# Motherboard.net
KiCad netlist of a schematic drawn in EAGLE
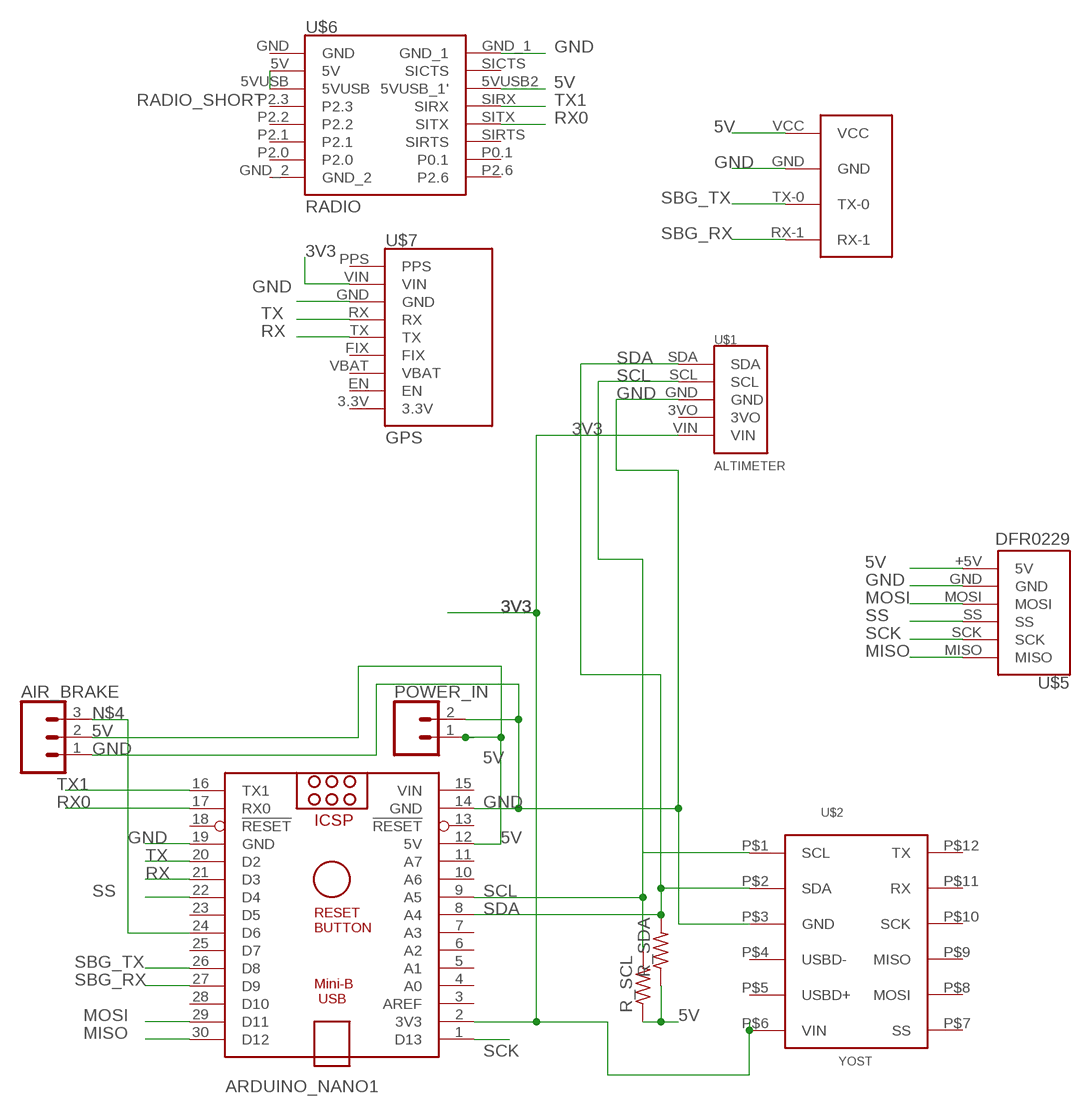
[diagram p0: schematic, sheet 1]

(export (version "E")
  (design (tool "Eeschema 10.0.6"))
  (components
    (comp (ref "AIR_BRAKE")
      (value "CONN_03")
      (footprint "eagle-import:1X03")
      (libsource (lib "eagle-import") (part "CONN_03"))
    )
    (comp (ref "ARDUINO_NANO1")
      (value "ARDUINO_NANO")
      (footprint "eagle-import:ARDUINO_NANO")
      (libsource (lib "eagle-import") (part "ARDUINO_NANO"))
    )
    (comp (ref "POWER_IN")
      (value "CONN_023.5MM")
      (footprint "eagle-import:SCREWTERMINAL-3.5MM-2")
      (libsource (lib "eagle-import") (part "CONN_023.5MM"))
    )
    (comp (ref "R_SCL")
      (value "R-US_R0603")
      (footprint "eagle-import:R0603")
      (libsource (lib "eagle-import") (part "R-US_R0603"))
    )
    (comp (ref "R_SDA")
      (value "R-US_R0603")
      (footprint "eagle-import:R0603")
      (libsource (lib "eagle-import") (part "R-US_R0603"))
    )
    (comp (ref "U$1")
      (value "ALTIMETER")
      (footprint "eagle-import:ALTIMETER")
      (libsource (lib "eagle-import") (part "ALTIMETER"))
    )
    (comp (ref "U$2")
      (value "YOST")
      (footprint "eagle-import:YOST")
      (libsource (lib "eagle-import") (part "YOST"))
    )
    (comp (ref "U$3")
      (value "RS232")
      (footprint "eagle-import:RS232")
      (libsource (lib "eagle-import") (part "RS232"))
    )
    (comp (ref "U$5")
      (value "DFR0229")
      (footprint "eagle-import:DFR0229")
      (libsource (lib "eagle-import") (part "DFR0229"))
    )
    (comp (ref "U$6")
      (value "RADIO")
      (footprint "eagle-import:RADIO")
      (libsource (lib "eagle-import") (part "RADIO"))
    )
    (comp (ref "U$7")
      (value "GPS")
      (footprint "eagle-import:GPS")
      (libsource (lib "eagle-import") (part "GPS"))
    )
  )
  (nets
    (net (code "1") (name "/3V3") (class "Default")
      (node (ref "ARDUINO_NANO1") (pin "2") (pinfunction "3V3_2") (pintype "output"))
      (node (ref "U$1") (pin "VIN") (pinfunction "VIN_VIN") (pintype "bidirectional"))
      (node (ref "U$2") (pin "P$6") (pinfunction "VIN_P$6") (pintype "bidirectional"))
      (node (ref "U$7") (pin "VIN") (pinfunction "VIN_VIN") (pintype "bidirectional"))
    )
    (net (code "2") (name "/5V") (class "Default")
      (node (ref "AIR_BRAKE") (pin "2") (pinfunction "2_2") (pintype "passive"))
      (node (ref "ARDUINO_NANO1") (pin "12") (pinfunction "5V_12") (pintype "power_in"))
      (node (ref "POWER_IN") (pin "1") (pinfunction "1_1") (pintype "passive"))
      (node (ref "R_SCL") (pin "1") (pinfunction "1_1") (pintype "passive"))
      (node (ref "R_SDA") (pin "1") (pinfunction "1_1") (pintype "passive"))
      (node (ref "U$3") (pin "VCC") (pinfunction "VCC_VCC") (pintype "bidirectional"))
      (node (ref "U$5") (pin "+5V") (pinfunction "5V_+5V") (pintype "bidirectional"))
      (node (ref "U$6") (pin "5VUSB2") (pinfunction "5VUSB_1'_5VUSB2") (pintype "bidirectional"))
    )
    (net (code "3") (name "/GND") (class "Default")
      (node (ref "AIR_BRAKE") (pin "1") (pinfunction "1_1") (pintype "passive"))
      (node (ref "ARDUINO_NANO1") (pin "14") (pinfunction "GND_14") (pintype "power_in"))
      (node (ref "ARDUINO_NANO1") (pin "19") (pinfunction "GND_19") (pintype "power_in"))
      (node (ref "POWER_IN") (pin "2") (pinfunction "2_2") (pintype "passive"))
      (node (ref "U$1") (pin "GND") (pinfunction "GND_GND") (pintype "bidirectional"))
      (node (ref "U$2") (pin "P$3") (pinfunction "GND_P$3") (pintype "bidirectional"))
      (node (ref "U$3") (pin "GND") (pinfunction "GND_GND") (pintype "bidirectional"))
      (node (ref "U$5") (pin "GND") (pinfunction "GND_GND") (pintype "bidirectional"))
      (node (ref "U$6") (pin "GND_1") (pinfunction "GND_1_GND_1") (pintype "bidirectional"))
      (node (ref "U$7") (pin "GND") (pinfunction "GND_GND") (pintype "bidirectional"))
    )
    (net (code "4") (name "/MISO") (class "Default")
      (node (ref "ARDUINO_NANO1") (pin "30") (pinfunction "D12_30") (pintype "bidirectional"))
      (node (ref "U$5") (pin "MISO") (pinfunction "MISO_MISO") (pintype "bidirectional"))
    )
    (net (code "5") (name "/MOSI") (class "Default")
      (node (ref "ARDUINO_NANO1") (pin "29") (pinfunction "D11_29") (pintype "bidirectional"))
      (node (ref "U$5") (pin "MOSI") (pinfunction "MOSI_MOSI") (pintype "bidirectional"))
    )
    (net (code "6") (name "/N$4") (class "Default")
      (node (ref "AIR_BRAKE") (pin "3") (pinfunction "3_3") (pintype "passive"))
      (node (ref "ARDUINO_NANO1") (pin "24") (pinfunction "D6_24") (pintype "bidirectional"))
    )
    (net (code "7") (name "/RADIO_SHORT") (class "Default")
      (node (ref "U$6") (pin "5V") (pinfunction "5V_5V") (pintype "bidirectional"))
      (node (ref "U$6") (pin "5VUSB") (pinfunction "5VUSB_5VUSB") (pintype "bidirectional"))
    )
    (net (code "8") (name "/RX") (class "Default")
      (node (ref "ARDUINO_NANO1") (pin "21") (pinfunction "D3_21") (pintype "bidirectional"))
      (node (ref "U$7") (pin "TX") (pinfunction "TX_TX") (pintype "bidirectional"))
    )
    (net (code "9") (name "/RX0") (class "Default")
      (node (ref "ARDUINO_NANO1") (pin "17") (pinfunction "RX0_17") (pintype "bidirectional"))
      (node (ref "U$6") (pin "SITX") (pinfunction "SITX_SITX") (pintype "bidirectional"))
    )
    (net (code "10") (name "/SBG_RX") (class "Default")
      (node (ref "ARDUINO_NANO1") (pin "27") (pinfunction "D9_27") (pintype "bidirectional"))
      (node (ref "U$3") (pin "RX-1") (pinfunction "RX-1_RX-1") (pintype "bidirectional"))
    )
    (net (code "11") (name "/SBG_TX") (class "Default")
      (node (ref "ARDUINO_NANO1") (pin "26") (pinfunction "D8_26") (pintype "bidirectional"))
      (node (ref "U$3") (pin "TX-0") (pinfunction "TX-0_TX-0") (pintype "bidirectional"))
    )
    (net (code "12") (name "/SCK") (class "Default")
      (node (ref "ARDUINO_NANO1") (pin "1") (pinfunction "D13_1") (pintype "bidirectional"))
      (node (ref "U$5") (pin "SCK") (pinfunction "SCK_SCK") (pintype "bidirectional"))
    )
    (net (code "13") (name "/SCL") (class "Default")
      (node (ref "ARDUINO_NANO1") (pin "9") (pinfunction "A5_9") (pintype "bidirectional"))
      (node (ref "R_SCL") (pin "2") (pinfunction "2_2") (pintype "passive"))
      (node (ref "U$1") (pin "SCL") (pinfunction "SCL_SCL") (pintype "bidirectional"))
      (node (ref "U$2") (pin "P$1") (pinfunction "SCL_P$1") (pintype "bidirectional"))
    )
    (net (code "14") (name "/SDA") (class "Default")
      (node (ref "ARDUINO_NANO1") (pin "8") (pinfunction "A4_8") (pintype "bidirectional"))
      (node (ref "R_SDA") (pin "2") (pinfunction "2_2") (pintype "passive"))
      (node (ref "U$1") (pin "SDA") (pinfunction "SDA_SDA") (pintype "bidirectional"))
      (node (ref "U$2") (pin "P$2") (pinfunction "SDA_P$2") (pintype "bidirectional"))
    )
    (net (code "15") (name "/SS") (class "Default")
      (node (ref "ARDUINO_NANO1") (pin "22") (pinfunction "D4_22") (pintype "bidirectional"))
      (node (ref "U$5") (pin "SS") (pinfunction "SS_SS") (pintype "bidirectional"))
    )
    (net (code "16") (name "/TX") (class "Default")
      (node (ref "ARDUINO_NANO1") (pin "20") (pinfunction "D2_20") (pintype "bidirectional"))
      (node (ref "U$7") (pin "RX") (pinfunction "RX_RX") (pintype "bidirectional"))
    )
    (net (code "17") (name "/TX1") (class "Default")
      (node (ref "ARDUINO_NANO1") (pin "16") (pinfunction "TX1_16") (pintype "bidirectional"))
      (node (ref "U$6") (pin "SIRX") (pinfunction "SIRX_SIRX") (pintype "bidirectional"))
    )
    (net (code "18") (name "/VIN") (class "Default")
      (node (ref "ARDUINO_NANO1") (pin "15") (pinfunction "VIN_15") (pintype "power_in"))
    )
    (net (code "19") (name "unconnected-(ARDUINO_NANO1-A0-Pad4)") (class "Default")
      (node (ref "ARDUINO_NANO1") (pin "4") (pinfunction "A0_4") (pintype "bidirectional"))
    )
    (net (code "20") (name "unconnected-(ARDUINO_NANO1-A1-Pad5)") (class "Default")
      (node (ref "ARDUINO_NANO1") (pin "5") (pinfunction "A1_5") (pintype "bidirectional"))
    )
    (net (code "21") (name "unconnected-(ARDUINO_NANO1-A2-Pad6)") (class "Default")
      (node (ref "ARDUINO_NANO1") (pin "6") (pinfunction "A2_6") (pintype "bidirectional"))
    )
    (net (code "22") (name "unconnected-(ARDUINO_NANO1-A3-Pad7)") (class "Default")
      (node (ref "ARDUINO_NANO1") (pin "7") (pinfunction "A3_7") (pintype "bidirectional"))
    )
    (net (code "23") (name "unconnected-(ARDUINO_NANO1-A6-Pad10)") (class "Default")
      (node (ref "ARDUINO_NANO1") (pin "10") (pinfunction "A6_10") (pintype "bidirectional"))
    )
    (net (code "24") (name "unconnected-(ARDUINO_NANO1-A7-Pad11)") (class "Default")
      (node (ref "ARDUINO_NANO1") (pin "11") (pinfunction "A7_11") (pintype "bidirectional"))
    )
    (net (code "25") (name "unconnected-(ARDUINO_NANO1-AREF-Pad3)") (class "Default")
      (node (ref "ARDUINO_NANO1") (pin "3") (pinfunction "AREF_3") (pintype "input"))
    )
    (net (code "26") (name "unconnected-(ARDUINO_NANO1-D5-Pad23)") (class "Default")
      (node (ref "ARDUINO_NANO1") (pin "23") (pinfunction "D5_23") (pintype "bidirectional"))
    )
    (net (code "27") (name "unconnected-(ARDUINO_NANO1-D7-Pad25)") (class "Default")
      (node (ref "ARDUINO_NANO1") (pin "25") (pinfunction "D7_25") (pintype "bidirectional"))
    )
    (net (code "28") (name "unconnected-(ARDUINO_NANO1-D10-Pad28)") (class "Default")
      (node (ref "ARDUINO_NANO1") (pin "28") (pinfunction "D10_28") (pintype "bidirectional"))
    )
    (net (code "29") (name "unconnected-(ARDUINO_NANO1-~{RESET}-Pad13)") (class "Default")
      (node (ref "ARDUINO_NANO1") (pin "13") (pinfunction "~{RESET}_13") (pintype "input"))
    )
    (net (code "30") (name "unconnected-(ARDUINO_NANO1-~{RESET}-Pad18)") (class "Default")
      (node (ref "ARDUINO_NANO1") (pin "18") (pinfunction "~{RESET}_18") (pintype "input"))
    )
    (net (code "31") (name "unconnected-(U$1-Pad3VO)") (class "Default")
      (node (ref "U$1") (pin "3VO") (pinfunction "3VO_3VO") (pintype "bidirectional"))
    )
    (net (code "32") (name "unconnected-(U$2-MISO-PadP$9)") (class "Default")
      (node (ref "U$2") (pin "P$9") (pinfunction "MISO_P$9") (pintype "bidirectional"))
    )
    (net (code "33") (name "unconnected-(U$2-MOSI-PadP$8)") (class "Default")
      (node (ref "U$2") (pin "P$8") (pinfunction "MOSI_P$8") (pintype "bidirectional"))
    )
    (net (code "34") (name "unconnected-(U$2-RX-PadP$11)") (class "Default")
      (node (ref "U$2") (pin "P$11") (pinfunction "RX_P$11") (pintype "bidirectional"))
    )
    (net (code "35") (name "unconnected-(U$2-SCK-PadP$10)") (class "Default")
      (node (ref "U$2") (pin "P$10") (pinfunction "SCK_P$10") (pintype "bidirectional"))
    )
    (net (code "36") (name "unconnected-(U$2-SS-PadP$7)") (class "Default")
      (node (ref "U$2") (pin "P$7") (pinfunction "SS_P$7") (pintype "bidirectional"))
    )
    (net (code "37") (name "unconnected-(U$2-TX-PadP$12)") (class "Default")
      (node (ref "U$2") (pin "P$12") (pinfunction "TX_P$12") (pintype "bidirectional"))
    )
    (net (code "38") (name "unconnected-(U$2-USBD+-PadP$5)") (class "Default")
      (node (ref "U$2") (pin "P$5") (pinfunction "USBD+_P$5") (pintype "bidirectional"))
    )
    (net (code "39") (name "unconnected-(U$2-USBD--PadP$4)") (class "Default")
      (node (ref "U$2") (pin "P$4") (pinfunction "USBD-_P$4") (pintype "bidirectional"))
    )
    (net (code "40") (name "unconnected-(U$6-PadGND)") (class "Default")
      (node (ref "U$6") (pin "GND") (pinfunction "GND_GND") (pintype "bidirectional"))
    )
    (net (code "41") (name "unconnected-(U$6-PadGND_2)") (class "Default")
      (node (ref "U$6") (pin "GND_2") (pinfunction "GND_2_GND_2") (pintype "bidirectional"))
    )
    (net (code "42") (name "unconnected-(U$6-PadP0.1)") (class "Default")
      (node (ref "U$6") (pin "P0.1") (pinfunction "P0.1_P0.1") (pintype "bidirectional"))
    )
    (net (code "43") (name "unconnected-(U$6-PadP2.0)") (class "Default")
      (node (ref "U$6") (pin "P2.0") (pinfunction "P2.0_P2.0") (pintype "bidirectional"))
    )
    (net (code "44") (name "unconnected-(U$6-PadP2.1)") (class "Default")
      (node (ref "U$6") (pin "P2.1") (pinfunction "P2.1_P2.1") (pintype "bidirectional"))
    )
    (net (code "45") (name "unconnected-(U$6-PadP2.2)") (class "Default")
      (node (ref "U$6") (pin "P2.2") (pinfunction "P2.2_P2.2") (pintype "bidirectional"))
    )
    (net (code "46") (name "unconnected-(U$6-PadP2.3)") (class "Default")
      (node (ref "U$6") (pin "P2.3") (pinfunction "P2.3_P2.3") (pintype "bidirectional"))
    )
    (net (code "47") (name "unconnected-(U$6-PadP2.6)") (class "Default")
      (node (ref "U$6") (pin "P2.6") (pinfunction "P2.6_P2.6") (pintype "bidirectional"))
    )
    (net (code "48") (name "unconnected-(U$6-PadSICTS)") (class "Default")
      (node (ref "U$6") (pin "SICTS") (pinfunction "SICTS_SICTS") (pintype "bidirectional"))
    )
    (net (code "49") (name "unconnected-(U$6-PadSIRTS)") (class "Default")
      (node (ref "U$6") (pin "SIRTS") (pinfunction "SIRTS_SIRTS") (pintype "bidirectional"))
    )
    (net (code "50") (name "unconnected-(U$7-Pad3.3V)") (class "Default")
      (node (ref "U$7") (pin "3.3V") (pinfunction "3.3V_3.3V") (pintype "bidirectional"))
    )
    (net (code "51") (name "unconnected-(U$7-PadEN)") (class "Default")
      (node (ref "U$7") (pin "EN") (pinfunction "EN_EN") (pintype "bidirectional"))
    )
    (net (code "52") (name "unconnected-(U$7-PadFIX)") (class "Default")
      (node (ref "U$7") (pin "FIX") (pinfunction "FIX_FIX") (pintype "bidirectional"))
    )
    (net (code "53") (name "unconnected-(U$7-PadPPS)") (class "Default")
      (node (ref "U$7") (pin "PPS") (pinfunction "PPS_PPS") (pintype "bidirectional"))
    )
    (net (code "54") (name "unconnected-(U$7-PadVBAT)") (class "Default")
      (node (ref "U$7") (pin "VBAT") (pinfunction "VBAT_VBAT") (pintype "bidirectional"))
    )
  )
)
